# Shield_Amir_ELAD_V_0_0.net
KiCad netlist of a schematic drawn in EasyEDA
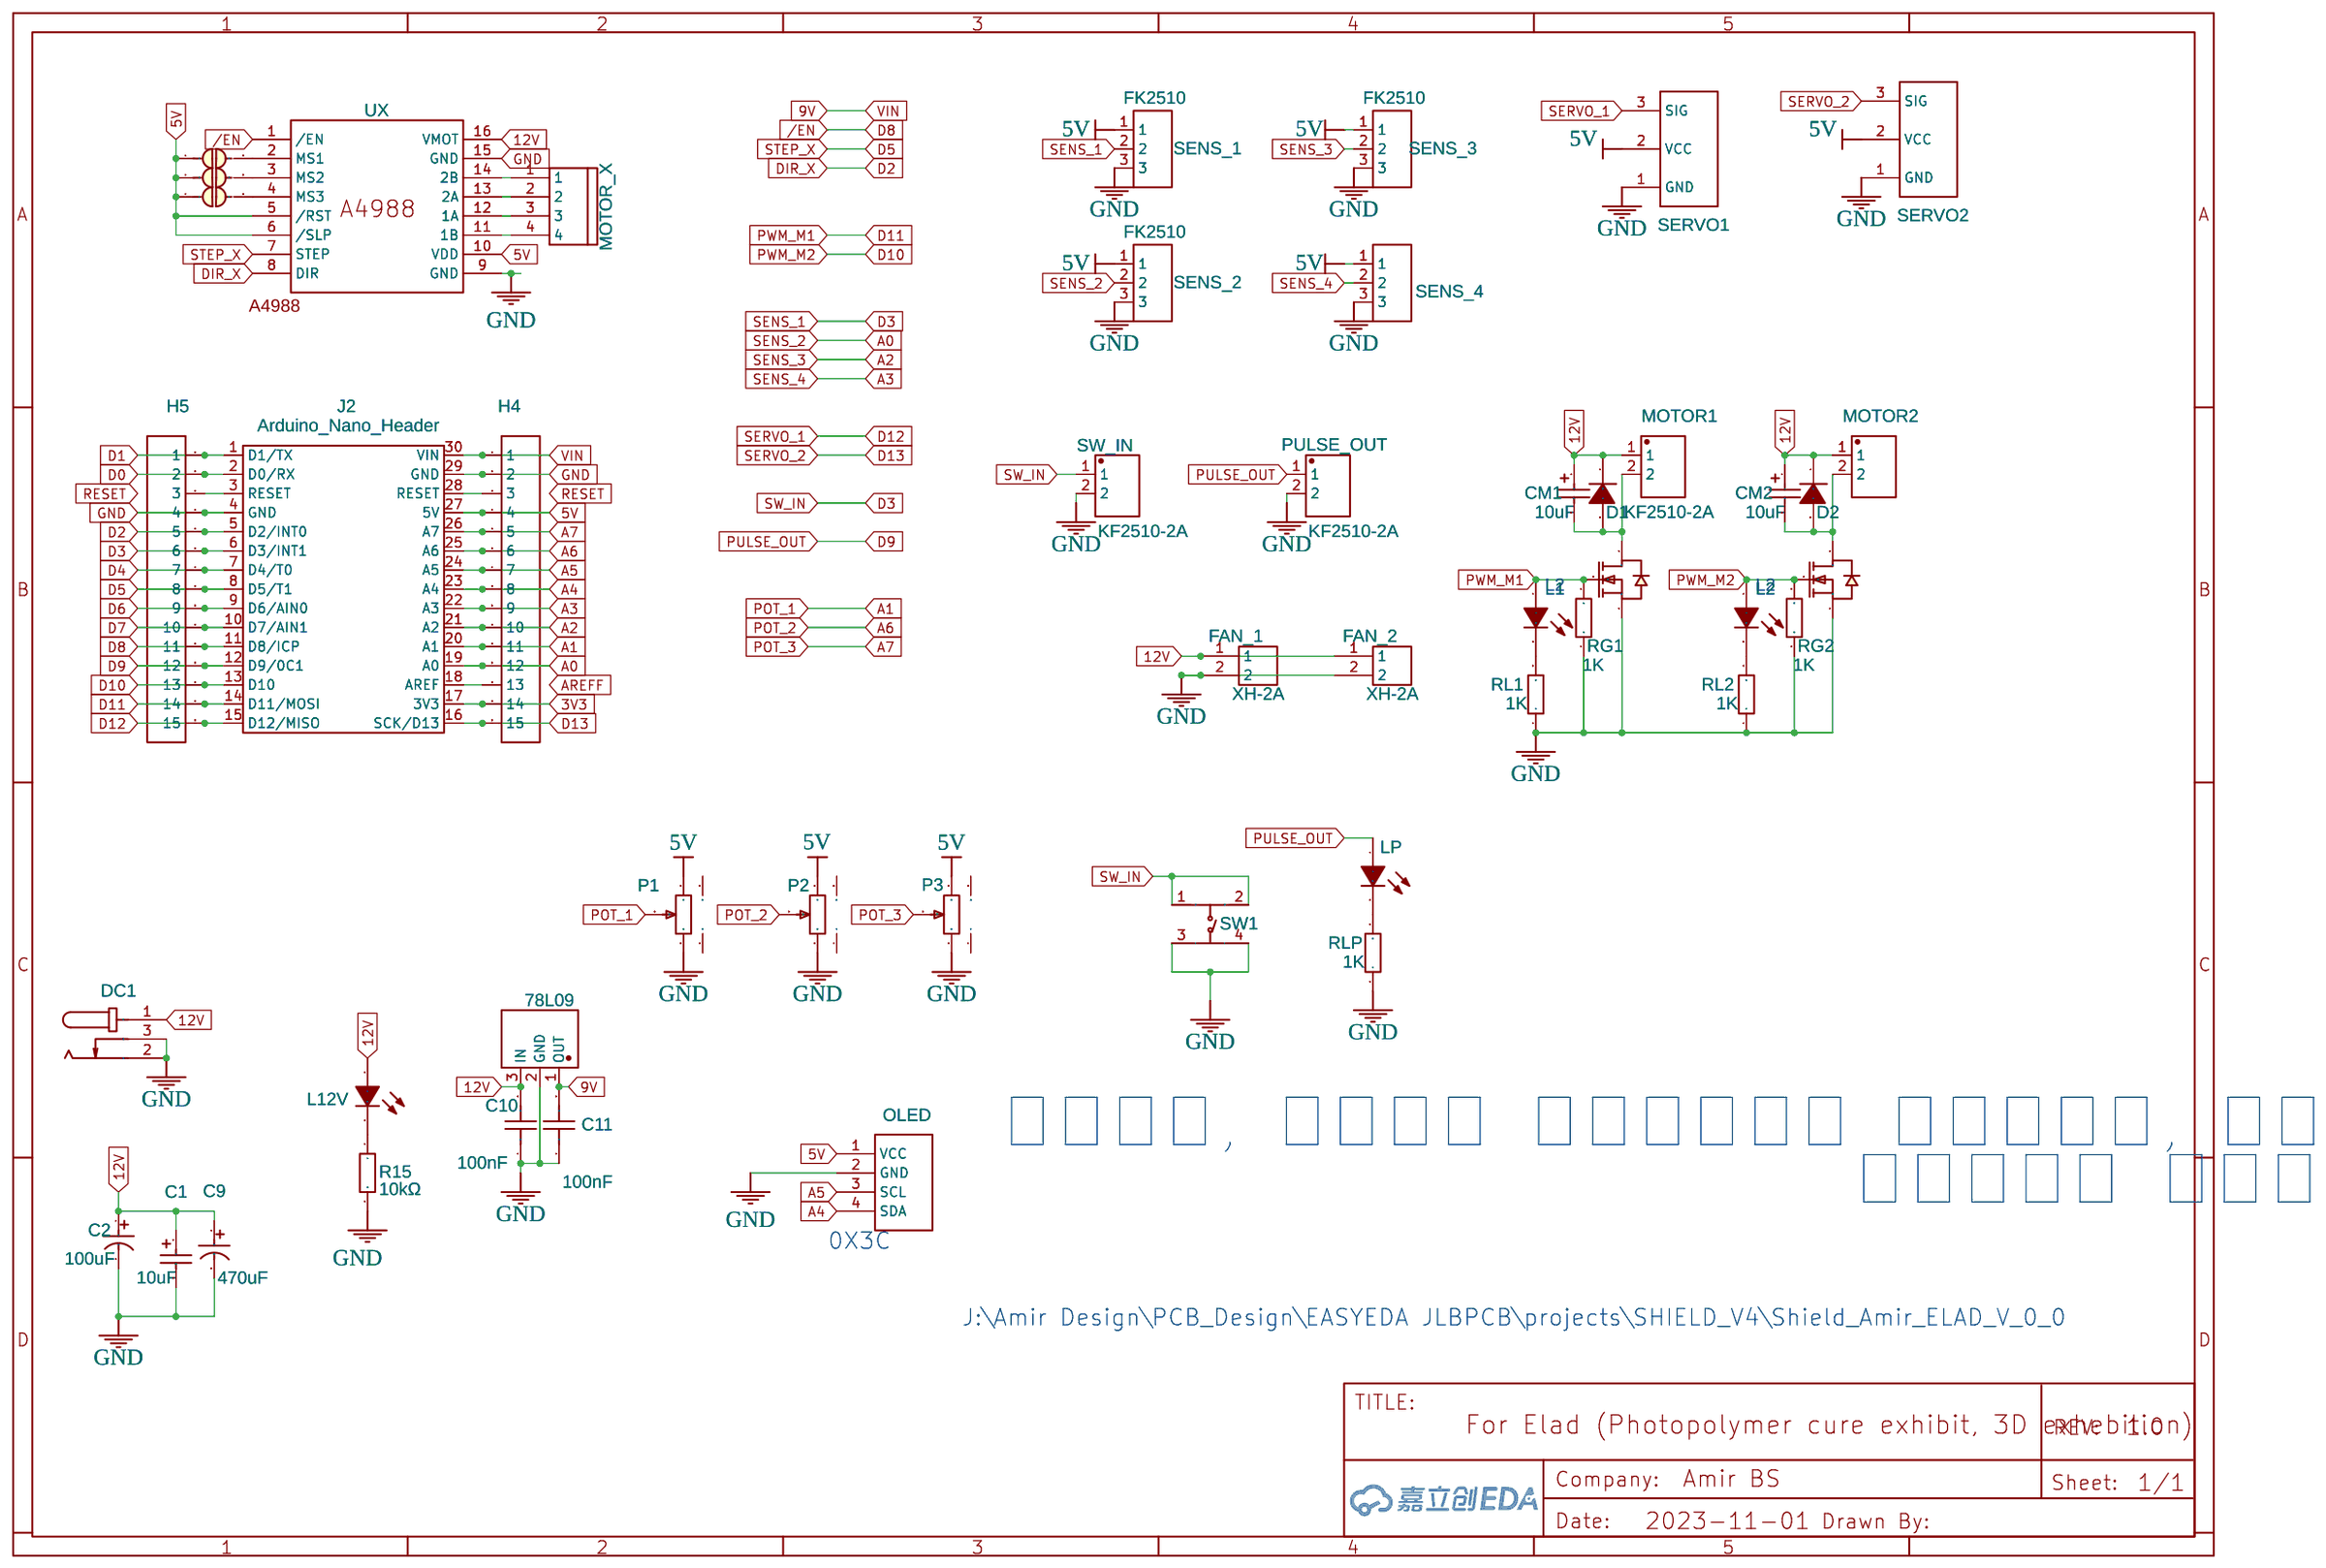
[diagram p0: schematic sheet]

(export (version "E")
  (design (tool "Eeschema 10.0.6"))
  (components
    (comp (ref "C1")
      (value "10uF")
      (fields (field (name "Manufacturer Part") "TAJA106K016RNJ") (field (name "Manufacturer") "Kyocera AVX"))
      (libsource (lib "") (part "TAJA106K016RNJ_1"))
    )
    (comp (ref "C2")
      (value "100uF")
      (fields
        (field (name "Manufacturer Part") "KM107M035E11RR0VH2FP0")
        (field (name "Manufacturer") "CX(承兴)")
      )
      (libsource (lib "") (part "100uF 35V 6.3*11"))
    )
    (comp (ref "C9")
      (value "470uF")
      (fields
        (field (name "Manufacturer Part") "GR477M025F12RR0VH4FP0")
        (field (name "Manufacturer") "CX(承兴)")
      )
      (libsource (lib "") (part "470uF 25V 8*12Black high frequency"))
    )
    (comp (ref "C10")
      (value "100nF")
      (fields
        (field (name "Manufacturer Part") "CC0603KRX7R9BB104")
        (field (name "Manufacturer") "YAGEO(国巨)")
      )
      (libsource (lib "") (part "CC0603KRX7R9BB104"))
    )
    (comp (ref "C11")
      (value "100nF")
      (fields
        (field (name "Manufacturer Part") "CC0603KRX7R9BB104")
        (field (name "Manufacturer") "YAGEO(国巨)")
      )
      (libsource (lib "") (part "CC0603KRX7R9BB104"))
    )
    (comp (ref "CM1")
      (value "10uF")
      (fields (field (name "Manufacturer Part") "TAJA106K016RNJ") (field (name "Manufacturer") "Kyocera AVX"))
      (libsource (lib "") (part "TAJA106K016RNJ"))
    )
    (comp (ref "CM2")
      (value "10uF")
      (fields (field (name "Manufacturer Part") "TAJA106K016RNJ") (field (name "Manufacturer") "Kyocera AVX"))
      (libsource (lib "") (part "TAJA106K016RNJ"))
    )
    (comp (ref "D1")
      (value "1N4007")
      (fields (field (name "BOM_Manufacturer Part") "1N4007F") (field (name "BOM_Supplier Part") "C110856"))
      (libsource (lib "") (part "1N4007F"))
    )
    (comp (ref "D2")
      (value "1N4007")
      (fields (field (name "BOM_Manufacturer Part") "1N4007F") (field (name "BOM_Supplier Part") "C110856"))
      (libsource (lib "") (part "1N4007F"))
    )
    (comp (ref "DC1")
      (value "DC")
      (fields
        (field (name "BOM_Manufacturer Part") "DC005-2.0MM")
        (field (name "BOM_Supplier Part") "C111567")
      )
      (libsource (lib "") (part "DC005-2.0MM"))
    )
    (comp (ref "FAN_1")
      (value "XH-2A")
      (fields (field (name "Manufacturer") "BOOMELE(博穆精密)"))
      (libsource (lib "") (part "XH-2A"))
    )
    (comp (ref "FAN_2")
      (value "XH-2A")
      (fields (field (name "Manufacturer") "BOOMELE(博穆精密)"))
      (libsource (lib "") (part "XH-2A"))
    )
    (comp (ref "H4")
      (value "HDR-F-2.54_1x15")
      (fields (field (name "BOM_Supplier Part") "C124408"))
      (libsource (lib "") (part "HDR-F-2.54_1x15"))
    )
    (comp (ref "H5")
      (value "HDR-F-2.54_1x15")
      (fields (field (name "BOM_Supplier Part") "C124408"))
      (libsource (lib "") (part "HDR-F-2.54_1x15_1"))
    )
    (comp (ref "J2") (value "Arduino_Nano_Header") (libsource (lib "") (part "Arduino_Nano_Header")))
    (comp (ref "JX1") (value "JUMPER-SMT_2") (libsource (lib "") (part "JUMPER-SMT_2")))
    (comp (ref "JX2") (value "JUMPER-SMT_2") (libsource (lib "") (part "JUMPER-SMT_2")))
    (comp (ref "JX3") (value "JUMPER-SMT_2") (libsource (lib "") (part "JUMPER-SMT_2")))
    (comp (ref "L1")
      (value "LED")
      (fields
        (field (name "BOM_Manufacturer Part") "19-217/BHC-ZL1M2RY/3T")
        (field (name "BOM_Supplier Part") "C72041")
      )
      (libsource (lib "") (part "19-217/BHC-ZL1M2RY/3T_2"))
    )
    (comp (ref "L2")
      (value "LED")
      (fields
        (field (name "BOM_Manufacturer Part") "19-217/BHC-ZL1M2RY/3T")
        (field (name "BOM_Supplier Part") "C72041")
      )
      (libsource (lib "") (part "19-217/BHC-ZL1M2RY/3T_2"))
    )
    (comp (ref "L12V")
      (value "LED")
      (fields
        (field (name "BOM_Manufacturer Part") "19-217/BHC-ZL1M2RY/3T")
        (field (name "BOM_Supplier Part") "C72041")
      )
      (libsource (lib "") (part "19-217/BHC-ZL1M2RY/3T_1"))
    )
    (comp (ref "LP")
      (value "LED")
      (fields
        (field (name "BOM_Manufacturer Part") "19-217/BHC-ZL1M2RY/3T")
        (field (name "BOM_Supplier Part") "C72041")
      )
      (libsource (lib "") (part "19-217/BHC-ZL1M2RY/3T"))
    )
    (comp (ref "MOTOR1")
      (value "KF2510-2A")
      (fields (field (name "BOM_Supplier Part") "C27543"))
      (libsource (lib "") (part "KF2510-2A_1"))
    )
    (comp (ref "MOTOR2")
      (value "KF2510-2A")
      (fields (field (name "BOM_Supplier Part") "C27543"))
      (libsource (lib "") (part "KF2510-2A_1"))
    )
    (comp (ref "MOTOR_X")
      (value "XH2.54-4AW")
      (fields (field (name "Manufacturer Part") "XH-4AW") (field (name "Manufacturer") "BOOMELE(博穆精密)"))
      (libsource (lib "") (part "XH2.54-4AW"))
    )
    (comp (ref "OLED")
      (value "1.3 inch OLED SSH1106 I2C 128x64 copy")
      (libsource (lib "") (part "1.3 inch OLED SSH1106 I2C 128x64 copy"))
    )
    (comp (ref "P1")
      (value "长柄旋转电位器")
      (fields (field (name "BOM_Supplier Part") "C2874842"))
      (libsource (lib "") (part "长柄旋转电位器"))
    )
    (comp (ref "P2")
      (value "长柄旋转电位器")
      (fields (field (name "BOM_Supplier Part") "C2874842"))
      (libsource (lib "") (part "长柄旋转电位器"))
    )
    (comp (ref "P3")
      (value "长柄旋转电位器")
      (fields (field (name "BOM_Supplier Part") "C2874842"))
      (libsource (lib "") (part "长柄旋转电位器"))
    )
    (comp (ref "PULSE_OUT")
      (value "KF2510-2A")
      (fields (field (name "BOM_Supplier Part") "C27543"))
      (libsource (lib "") (part "KF2510-2A"))
    )
    (comp (ref "Q1")
      (value "Q")
      (fields (field (name "BOM_Manufacturer Part") "JSM2302") (field (name "BOM_Supplier Part") "C916403"))
      (libsource (lib "") (part "JSM2302"))
    )
    (comp (ref "Q2")
      (value "Q")
      (fields (field (name "BOM_Manufacturer Part") "JSM2302") (field (name "BOM_Supplier Part") "C916403"))
      (libsource (lib "") (part "JSM2302"))
    )
    (comp (ref "R15")
      (value "10kΩ")
      (fields
        (field (name "BOM_Manufacturer Part") "0603WAF1002T5E")
        (field (name "BOM_Supplier Part") "C25804")
      )
      (libsource (lib "") (part "0603WAF1002T5E"))
    )
    (comp (ref "RG1")
      (value "1K")
      (fields
        (field (name "BOM_Manufacturer Part") "0603WAF1001T5E")
        (field (name "BOM_Supplier Part") "C21190")
      )
      (libsource (lib "") (part "0603WAF1001T5E_2"))
    )
    (comp (ref "RG2")
      (value "1K")
      (fields
        (field (name "BOM_Manufacturer Part") "0603WAF1001T5E")
        (field (name "BOM_Supplier Part") "C21190")
      )
      (libsource (lib "") (part "0603WAF1001T5E_2"))
    )
    (comp (ref "RL1")
      (value "1K")
      (fields
        (field (name "BOM_Manufacturer Part") "0603WAF1001T5E")
        (field (name "BOM_Supplier Part") "C21190")
      )
      (libsource (lib "") (part "0603WAF1001T5E"))
    )
    (comp (ref "RL2")
      (value "1K")
      (fields
        (field (name "BOM_Manufacturer Part") "0603WAF1001T5E")
        (field (name "BOM_Supplier Part") "C21190")
      )
      (libsource (lib "") (part "0603WAF1001T5E"))
    )
    (comp (ref "RLP")
      (value "1K")
      (fields
        (field (name "BOM_Manufacturer Part") "0603WAF1001T5E")
        (field (name "BOM_Supplier Part") "C21190")
      )
      (libsource (lib "") (part "0603WAF1001T5E_1"))
    )
    (comp (ref "SENS_1")
      (value "FK2510")
      (fields (field (name "Manufacturer Part") "2510-3A") (field (name "Manufacturer") "BOOMELE(博穆精密)"))
      (libsource (lib "") (part "kf2510_3A"))
    )
    (comp (ref "SENS_2")
      (value "FK2510")
      (fields (field (name "Manufacturer Part") "2510-3A") (field (name "Manufacturer") "BOOMELE(博穆精密)"))
      (libsource (lib "") (part "kf2510_3A"))
    )
    (comp (ref "SENS_3")
      (value "FK2510")
      (fields (field (name "Manufacturer Part") "2510-3A") (field (name "Manufacturer") "BOOMELE(博穆精密)"))
      (libsource (lib "") (part "kf2510_3A"))
    )
    (comp (ref "SENS_4")
      (value "FK2510")
      (fields (field (name "Manufacturer Part") "2510-3A") (field (name "Manufacturer") "BOOMELE(博穆精密)"))
      (libsource (lib "") (part "kf2510_3A"))
    )
    (comp (ref "SERVO1")
      (value "Servo+3d")
      (fields (field (name "BOM_Manufacturer Part") "New SchematicLib"))
      (libsource (lib "") (part "Servo+3d"))
    )
    (comp (ref "SERVO2")
      (value "Servo+3d")
      (fields (field (name "BOM_Manufacturer Part") "New SchematicLib"))
      (libsource (lib "") (part "Servo+3d"))
    )
    (comp (ref "SW1")
      (value "TC-6610-7-160G")
      (fields (field (name "Manufacturer") "HCTL(华灿天禄)"))
      (libsource (lib "") (part "TC-6610-7-160G"))
    )
    (comp (ref "SW_IN")
      (value "KF2510-2A")
      (fields (field (name "BOM_Supplier Part") "C27543"))
      (libsource (lib "") (part "KF2510-2A_2"))
    )
    (comp (ref "U5")
      (value "78L09")
      (fields (field (name "Manufacturer Part") "78L09U 78L09") (field (name "Manufacturer") "CBI(创基)"))
      (libsource (lib "") (part "78L09U 78L09"))
    )
    (comp (ref "UX") (value "A4988") (libsource (lib "") (part "A4988")))
  )
  (nets
    (net (code "1") (name "3V3") (class "Default")
      (node (ref "H4") (pin "14") (pinfunction "14_14") (pintype "unspecified"))
      (node (ref "J2") (pin "17") (pinfunction "3V3_17") (pintype "unspecified"))
    )
    (net (code "2") (name "5V") (class "Default")
      (node (ref "H4") (pin "4") (pinfunction "4_4") (pintype "unspecified"))
      (node (ref "J2") (pin "27") (pinfunction "5V_27") (pintype "unspecified"))
      (node (ref "JX1") (pin "1") (pinfunction "1_1") (pintype "bidirectional"))
      (node (ref "JX2") (pin "1") (pinfunction "1_1") (pintype "bidirectional"))
      (node (ref "JX3") (pin "1") (pinfunction "1_1") (pintype "bidirectional"))
      (node (ref "OLED") (pin "1") (pinfunction "VCC_1") (pintype "passive"))
      (node (ref "P1") (pin "3") (pinfunction "3_3") (pintype "input"))
      (node (ref "P2") (pin "3") (pinfunction "3_3") (pintype "input"))
      (node (ref "P3") (pin "3") (pinfunction "3_3") (pintype "input"))
      (node (ref "SENS_1") (pin "1") (pinfunction "1_1") (pintype "unspecified"))
      (node (ref "SENS_2") (pin "1") (pinfunction "1_1") (pintype "unspecified"))
      (node (ref "SENS_3") (pin "1") (pinfunction "1_1") (pintype "unspecified"))
      (node (ref "SENS_4") (pin "1") (pinfunction "1_1") (pintype "unspecified"))
      (node (ref "SERVO1") (pin "2") (pinfunction "VCC_2") (pintype "unspecified"))
      (node (ref "SERVO2") (pin "2") (pinfunction "VCC_2") (pintype "unspecified"))
      (node (ref "UX") (pin "10") (pinfunction "VDD_10") (pintype "unspecified"))
      (node (ref "UX") (pin "5") (pinfunction "/RST_5") (pintype "unspecified"))
      (node (ref "UX") (pin "6") (pinfunction "/SLP_6") (pintype "unspecified"))
    )
    (net (code "3") (name "9V") (class "Default")
      (node (ref "C11") (pin "2") (pinfunction "2_2") (pintype "unspecified"))
      (node (ref "H4") (pin "1") (pinfunction "1_1") (pintype "unspecified"))
      (node (ref "J2") (pin "30") (pinfunction "VIN_30") (pintype "unspecified"))
      (node (ref "U5") (pin "1") (pinfunction "OUT_1") (pintype "unspecified"))
    )
    (net (code "4") (name "12V") (class "Default")
      (node (ref "C1") (pin "1") (pinfunction "1_1") (pintype "input"))
      (node (ref "C10") (pin "2") (pinfunction "2_2") (pintype "unspecified"))
      (node (ref "C2") (pin "1") (pinfunction "1_1") (pintype "input"))
      (node (ref "C9") (pin "1") (pinfunction "1_1") (pintype "input"))
      (node (ref "CM1") (pin "1") (pinfunction "1_1") (pintype "input"))
      (node (ref "CM2") (pin "1") (pinfunction "1_1") (pintype "input"))
      (node (ref "D1") (pin "1") (pinfunction "C_1") (pintype "unspecified"))
      (node (ref "D2") (pin "1") (pinfunction "C_1") (pintype "unspecified"))
      (node (ref "DC1") (pin "1") (pinfunction "1_1") (pintype "unspecified"))
      (node (ref "FAN_1") (pin "1") (pinfunction "1_1") (pintype "unspecified"))
      (node (ref "FAN_2") (pin "1") (pinfunction "1_1") (pintype "unspecified"))
      (node (ref "L12V") (pin "1") (pinfunction "A_1") (pintype "input"))
      (node (ref "MOTOR1") (pin "1") (pinfunction "1_1") (pintype "unspecified"))
      (node (ref "MOTOR2") (pin "1") (pinfunction "1_1") (pintype "unspecified"))
      (node (ref "U5") (pin "3") (pinfunction "IN_3") (pintype "unspecified"))
      (node (ref "UX") (pin "16") (pinfunction "VMOT_16") (pintype "unspecified"))
    )
    (net (code "5") (name "A0") (class "Default")
      (node (ref "H4") (pin "12") (pinfunction "12_12") (pintype "unspecified"))
      (node (ref "J2") (pin "19") (pinfunction "A0_19") (pintype "unspecified"))
      (node (ref "SENS_2") (pin "2") (pinfunction "2_2") (pintype "unspecified"))
    )
    (net (code "6") (name "A1") (class "Default")
      (node (ref "H4") (pin "11") (pinfunction "11_11") (pintype "unspecified"))
      (node (ref "J2") (pin "20") (pinfunction "A1_20") (pintype "unspecified"))
      (node (ref "P1") (pin "2") (pinfunction "2_2") (pintype "input"))
    )
    (net (code "7") (name "A2") (class "Default")
      (node (ref "H4") (pin "10") (pinfunction "10_10") (pintype "unspecified"))
      (node (ref "J2") (pin "21") (pinfunction "A2_21") (pintype "unspecified"))
      (node (ref "SENS_3") (pin "2") (pinfunction "2_2") (pintype "unspecified"))
    )
    (net (code "8") (name "A3") (class "Default")
      (node (ref "H4") (pin "9") (pinfunction "9_9") (pintype "unspecified"))
      (node (ref "J2") (pin "22") (pinfunction "A3_22") (pintype "unspecified"))
      (node (ref "SENS_4") (pin "2") (pinfunction "2_2") (pintype "unspecified"))
    )
    (net (code "9") (name "A4") (class "Default")
      (node (ref "H4") (pin "8") (pinfunction "8_8") (pintype "unspecified"))
      (node (ref "J2") (pin "23") (pinfunction "A4_23") (pintype "unspecified"))
      (node (ref "OLED") (pin "4") (pinfunction "SDA_4") (pintype "bidirectional"))
    )
    (net (code "10") (name "A5") (class "Default")
      (node (ref "H4") (pin "7") (pinfunction "7_7") (pintype "unspecified"))
      (node (ref "J2") (pin "24") (pinfunction "A5_24") (pintype "unspecified"))
      (node (ref "OLED") (pin "3") (pinfunction "SCL_3") (pintype "bidirectional"))
    )
    (net (code "11") (name "A6") (class "Default")
      (node (ref "H4") (pin "6") (pinfunction "6_6") (pintype "unspecified"))
      (node (ref "J2") (pin "25") (pinfunction "A6_25") (pintype "unspecified"))
      (node (ref "P2") (pin "2") (pinfunction "2_2") (pintype "input"))
    )
    (net (code "12") (name "A7") (class "Default")
      (node (ref "H4") (pin "5") (pinfunction "5_5") (pintype "unspecified"))
      (node (ref "J2") (pin "26") (pinfunction "A7_26") (pintype "unspecified"))
      (node (ref "P3") (pin "2") (pinfunction "2_2") (pintype "input"))
    )
    (net (code "14") (name "D0") (class "Default")
      (node (ref "H5") (pin "2") (pinfunction "2_2") (pintype "unspecified"))
      (node (ref "J2") (pin "2") (pinfunction "D0/RX_2") (pintype "unspecified"))
    )
    (net (code "15") (name "D1") (class "Default")
      (node (ref "H5") (pin "1") (pinfunction "1_1") (pintype "unspecified"))
      (node (ref "J2") (pin "1") (pinfunction "D1/TX_1") (pintype "unspecified"))
    )
    (net (code "16") (name "D2") (class "Default")
      (node (ref "H5") (pin "5") (pinfunction "5_5") (pintype "unspecified"))
      (node (ref "J2") (pin "5") (pinfunction "D2/INT0_5") (pintype "unspecified"))
      (node (ref "UX") (pin "8") (pinfunction "DIR_8") (pintype "unspecified"))
    )
    (net (code "17") (name "D3") (class "Default")
      (node (ref "H5") (pin "6") (pinfunction "6_6") (pintype "unspecified"))
      (node (ref "J2") (pin "6") (pinfunction "D3/INT1_6") (pintype "unspecified"))
      (node (ref "SENS_1") (pin "2") (pinfunction "2_2") (pintype "unspecified"))
      (node (ref "SW1") (pin "1") (pinfunction "1_1") (pintype "unspecified"))
      (node (ref "SW1") (pin "2") (pinfunction "2_2") (pintype "unspecified"))
      (node (ref "SW_IN") (pin "1") (pinfunction "1_1") (pintype "unspecified"))
    )
    (net (code "18") (name "D4") (class "Default")
      (node (ref "H5") (pin "7") (pinfunction "7_7") (pintype "unspecified"))
      (node (ref "J2") (pin "7") (pinfunction "D4/T0_7") (pintype "unspecified"))
    )
    (net (code "19") (name "D5") (class "Default")
      (node (ref "H5") (pin "8") (pinfunction "8_8") (pintype "unspecified"))
      (node (ref "J2") (pin "8") (pinfunction "D5/T1_8") (pintype "unspecified"))
      (node (ref "UX") (pin "7") (pinfunction "STEP_7") (pintype "unspecified"))
    )
    (net (code "20") (name "D6") (class "Default")
      (node (ref "H5") (pin "9") (pinfunction "9_9") (pintype "unspecified"))
      (node (ref "J2") (pin "9") (pinfunction "D6/AIN0_9") (pintype "unspecified"))
    )
    (net (code "21") (name "D7") (class "Default")
      (node (ref "H5") (pin "10") (pinfunction "10_10") (pintype "unspecified"))
      (node (ref "J2") (pin "10") (pinfunction "D7/AIN1_10") (pintype "unspecified"))
    )
    (net (code "22") (name "D8") (class "Default")
      (node (ref "H5") (pin "11") (pinfunction "11_11") (pintype "unspecified"))
      (node (ref "J2") (pin "11") (pinfunction "D8/ICP_11") (pintype "unspecified"))
      (node (ref "UX") (pin "1") (pinfunction "/EN_1") (pintype "unspecified"))
    )
    (net (code "23") (name "D9") (class "Default")
      (node (ref "H5") (pin "12") (pinfunction "12_12") (pintype "unspecified"))
      (node (ref "J2") (pin "12") (pinfunction "D9/0C1_12") (pintype "unspecified"))
      (node (ref "LP") (pin "1") (pinfunction "A_1") (pintype "input"))
      (node (ref "PULSE_OUT") (pin "1") (pinfunction "1_1") (pintype "unspecified"))
    )
    (net (code "24") (name "D10") (class "Default")
      (node (ref "H5") (pin "13") (pinfunction "13_13") (pintype "unspecified"))
      (node (ref "J2") (pin "13") (pinfunction "D10_13") (pintype "unspecified"))
      (node (ref "L2") (pin "1") (pinfunction "A_1") (pintype "input"))
      (node (ref "Q2") (pin "1") (pinfunction "G_1") (pintype "unspecified"))
      (node (ref "RG2") (pin "2") (pinfunction "2_2") (pintype "input"))
    )
    (net (code "25") (name "D11") (class "Default")
      (node (ref "H5") (pin "14") (pinfunction "14_14") (pintype "unspecified"))
      (node (ref "J2") (pin "14") (pinfunction "D11/MOSI_14") (pintype "unspecified"))
      (node (ref "L1") (pin "1") (pinfunction "A_1") (pintype "input"))
      (node (ref "Q1") (pin "1") (pinfunction "G_1") (pintype "unspecified"))
      (node (ref "RG1") (pin "2") (pinfunction "2_2") (pintype "input"))
    )
    (net (code "26") (name "D12") (class "Default")
      (node (ref "H5") (pin "15") (pinfunction "15_15") (pintype "unspecified"))
      (node (ref "J2") (pin "15") (pinfunction "D12/MISO_15") (pintype "unspecified"))
      (node (ref "SERVO1") (pin "3") (pinfunction "SIG_3") (pintype "unspecified"))
    )
    (net (code "27") (name "D13") (class "Default")
      (node (ref "H4") (pin "15") (pinfunction "15_15") (pintype "unspecified"))
      (node (ref "J2") (pin "16") (pinfunction "SCK/D13_16") (pintype "unspecified"))
      (node (ref "SERVO2") (pin "3") (pinfunction "SIG_3") (pintype "unspecified"))
    )
    (net (code "28") (name "GND") (class "Default")
      (node (ref "C1") (pin "2") (pinfunction "2_2") (pintype "input"))
      (node (ref "C10") (pin "1") (pinfunction "1_1") (pintype "unspecified"))
      (node (ref "C11") (pin "1") (pinfunction "1_1") (pintype "unspecified"))
      (node (ref "C2") (pin "2") (pinfunction "2_2") (pintype "input"))
      (node (ref "C9") (pin "2") (pinfunction "2_2") (pintype "input"))
      (node (ref "DC1") (pin "2") (pinfunction "2_2") (pintype "unspecified"))
      (node (ref "DC1") (pin "3") (pinfunction "3_3") (pintype "unspecified"))
      (node (ref "FAN_1") (pin "2") (pinfunction "2_2") (pintype "unspecified"))
      (node (ref "FAN_2") (pin "2") (pinfunction "2_2") (pintype "unspecified"))
      (node (ref "H4") (pin "2") (pinfunction "2_2") (pintype "unspecified"))
      (node (ref "H5") (pin "4") (pinfunction "4_4") (pintype "unspecified"))
      (node (ref "J2") (pin "29") (pinfunction "GND_29") (pintype "unspecified"))
      (node (ref "J2") (pin "4") (pinfunction "GND_4") (pintype "unspecified"))
      (node (ref "OLED") (pin "2") (pinfunction "GND_2") (pintype "passive"))
      (node (ref "P1") (pin "1") (pinfunction "1_1") (pintype "input"))
      (node (ref "P2") (pin "1") (pinfunction "1_1") (pintype "input"))
      (node (ref "P3") (pin "1") (pinfunction "1_1") (pintype "input"))
      (node (ref "PULSE_OUT") (pin "2") (pinfunction "2_2") (pintype "unspecified"))
      (node (ref "Q1") (pin "2") (pinfunction "S_2") (pintype "unspecified"))
      (node (ref "Q2") (pin "2") (pinfunction "S_2") (pintype "unspecified"))
      (node (ref "R15") (pin "2") (pinfunction "2_2") (pintype "input"))
      (node (ref "RG1") (pin "1") (pinfunction "1_1") (pintype "input"))
      (node (ref "RG2") (pin "1") (pinfunction "1_1") (pintype "input"))
      (node (ref "RL1") (pin "1") (pinfunction "1_1") (pintype "input"))
      (node (ref "RL2") (pin "1") (pinfunction "1_1") (pintype "input"))
      (node (ref "RLP") (pin "1") (pinfunction "1_1") (pintype "input"))
      (node (ref "SENS_1") (pin "3") (pinfunction "3_3") (pintype "unspecified"))
      (node (ref "SENS_2") (pin "3") (pinfunction "3_3") (pintype "unspecified"))
      (node (ref "SENS_3") (pin "3") (pinfunction "3_3") (pintype "unspecified"))
      (node (ref "SENS_4") (pin "3") (pinfunction "3_3") (pintype "unspecified"))
      (node (ref "SERVO1") (pin "1") (pinfunction "GND_1") (pintype "unspecified"))
      (node (ref "SERVO2") (pin "1") (pinfunction "GND_1") (pintype "unspecified"))
      (node (ref "SW1") (pin "3") (pinfunction "3_3") (pintype "unspecified"))
      (node (ref "SW1") (pin "4") (pinfunction "4_4") (pintype "unspecified"))
      (node (ref "SW_IN") (pin "2") (pinfunction "2_2") (pintype "unspecified"))
      (node (ref "U5") (pin "2") (pinfunction "GND_2") (pintype "unspecified"))
      (node (ref "UX") (pin "15") (pinfunction "GND_15") (pintype "unspecified"))
      (node (ref "UX") (pin "9") (pinfunction "GND_9") (pintype "unspecified"))
    )
    (net (code "29") (name "Net-(D1-A)") (class "Default")
      (node (ref "CM1") (pin "2") (pinfunction "2_2") (pintype "input"))
      (node (ref "D1") (pin "2") (pinfunction "A_2") (pintype "unspecified"))
      (node (ref "MOTOR1") (pin "2") (pinfunction "2_2") (pintype "unspecified"))
      (node (ref "Q1") (pin "3") (pinfunction "D_3") (pintype "unspecified"))
    )
    (net (code "30") (name "Net-(D2-A)") (class "Default")
      (node (ref "CM2") (pin "2") (pinfunction "2_2") (pintype "input"))
      (node (ref "D2") (pin "2") (pinfunction "A_2") (pintype "unspecified"))
      (node (ref "MOTOR2") (pin "2") (pinfunction "2_2") (pintype "unspecified"))
      (node (ref "Q2") (pin "3") (pinfunction "D_3") (pintype "unspecified"))
    )
    (net (code "31") (name "Net-(H4-Pad3)") (class "Default")
      (node (ref "H4") (pin "3") (pinfunction "3_3") (pintype "unspecified"))
      (node (ref "J2") (pin "28") (pinfunction "RESET_28") (pintype "unspecified"))
    )
    (net (code "32") (name "Net-(H5-Pad3)") (class "Default")
      (node (ref "H5") (pin "3") (pinfunction "3_3") (pintype "unspecified"))
      (node (ref "J2") (pin "3") (pinfunction "RESET_3") (pintype "unspecified"))
    )
    (net (code "33") (name "Net-(J2-AREF)") (class "Default")
      (node (ref "H4") (pin "13") (pinfunction "13_13") (pintype "unspecified"))
      (node (ref "J2") (pin "18") (pinfunction "AREF_18") (pintype "unspecified"))
    )
    (net (code "34") (name "Net-(L1-C)") (class "Default")
      (node (ref "L1") (pin "2") (pinfunction "C_2") (pintype "input"))
      (node (ref "RL1") (pin "2") (pinfunction "2_2") (pintype "input"))
    )
    (net (code "35") (name "Net-(L2-C)") (class "Default")
      (node (ref "L2") (pin "2") (pinfunction "C_2") (pintype "input"))
      (node (ref "RL2") (pin "2") (pinfunction "2_2") (pintype "input"))
    )
    (net (code "36") (name "Net-(L12V-C)") (class "Default")
      (node (ref "L12V") (pin "2") (pinfunction "C_2") (pintype "input"))
      (node (ref "R15") (pin "1") (pinfunction "1_1") (pintype "input"))
    )
    (net (code "37") (name "Net-(LP-C)") (class "Default")
      (node (ref "LP") (pin "2") (pinfunction "C_2") (pintype "input"))
      (node (ref "RLP") (pin "2") (pinfunction "2_2") (pintype "input"))
    )
    (net (code "38") (name "Net-(UX-1A)") (class "Default")
      (node (ref "MOTOR_X") (pin "3") (pinfunction "3_3") (pintype "unspecified"))
      (node (ref "UX") (pin "12") (pinfunction "1A_12") (pintype "unspecified"))
    )
    (net (code "39") (name "Net-(UX-1B)") (class "Default")
      (node (ref "MOTOR_X") (pin "4") (pinfunction "4_4") (pintype "unspecified"))
      (node (ref "UX") (pin "11") (pinfunction "1B_11") (pintype "unspecified"))
    )
    (net (code "40") (name "Net-(UX-2A)") (class "Default")
      (node (ref "MOTOR_X") (pin "2") (pinfunction "2_2") (pintype "unspecified"))
      (node (ref "UX") (pin "13") (pinfunction "2A_13") (pintype "unspecified"))
    )
    (net (code "41") (name "Net-(UX-2B)") (class "Default")
      (node (ref "MOTOR_X") (pin "1") (pinfunction "1_1") (pintype "unspecified"))
      (node (ref "UX") (pin "14") (pinfunction "2B_14") (pintype "unspecified"))
    )
    (net (code "42") (name "Net-(UX-MS1)") (class "Default")
      (node (ref "JX1") (pin "2") (pinfunction "2_2") (pintype "bidirectional"))
      (node (ref "UX") (pin "2") (pinfunction "MS1_2") (pintype "unspecified"))
    )
    (net (code "43") (name "Net-(UX-MS2)") (class "Default")
      (node (ref "JX2") (pin "2") (pinfunction "2_2") (pintype "bidirectional"))
      (node (ref "UX") (pin "3") (pinfunction "MS2_3") (pintype "unspecified"))
    )
    (net (code "44") (name "Net-(UX-MS3)") (class "Default")
      (node (ref "JX3") (pin "2") (pinfunction "2_2") (pintype "bidirectional"))
      (node (ref "UX") (pin "4") (pinfunction "MS3_4") (pintype "unspecified"))
    )
    (net (code "46") (name "unconnected-(P1-Pad4)") (class "Default")
      (node (ref "P1") (pin "4") (pinfunction "4_4") (pintype "input"))
    )
    (net (code "47") (name "unconnected-(P1-Pad5)") (class "Default")
      (node (ref "P1") (pin "5") (pinfunction "5_5") (pintype "input"))
    )
    (net (code "48") (name "unconnected-(P2-Pad4)") (class "Default")
      (node (ref "P2") (pin "4") (pinfunction "4_4") (pintype "input"))
    )
    (net (code "49") (name "unconnected-(P2-Pad5)") (class "Default")
      (node (ref "P2") (pin "5") (pinfunction "5_5") (pintype "input"))
    )
    (net (code "50") (name "unconnected-(P3-Pad4)") (class "Default")
      (node (ref "P3") (pin "4") (pinfunction "4_4") (pintype "input"))
    )
    (net (code "51") (name "unconnected-(P3-Pad5)") (class "Default")
      (node (ref "P3") (pin "5") (pinfunction "5_5") (pintype "input"))
    )
  )
)
